# CubeSatPowerSupply.net
KiCad netlist of a schematic drawn in EAGLE
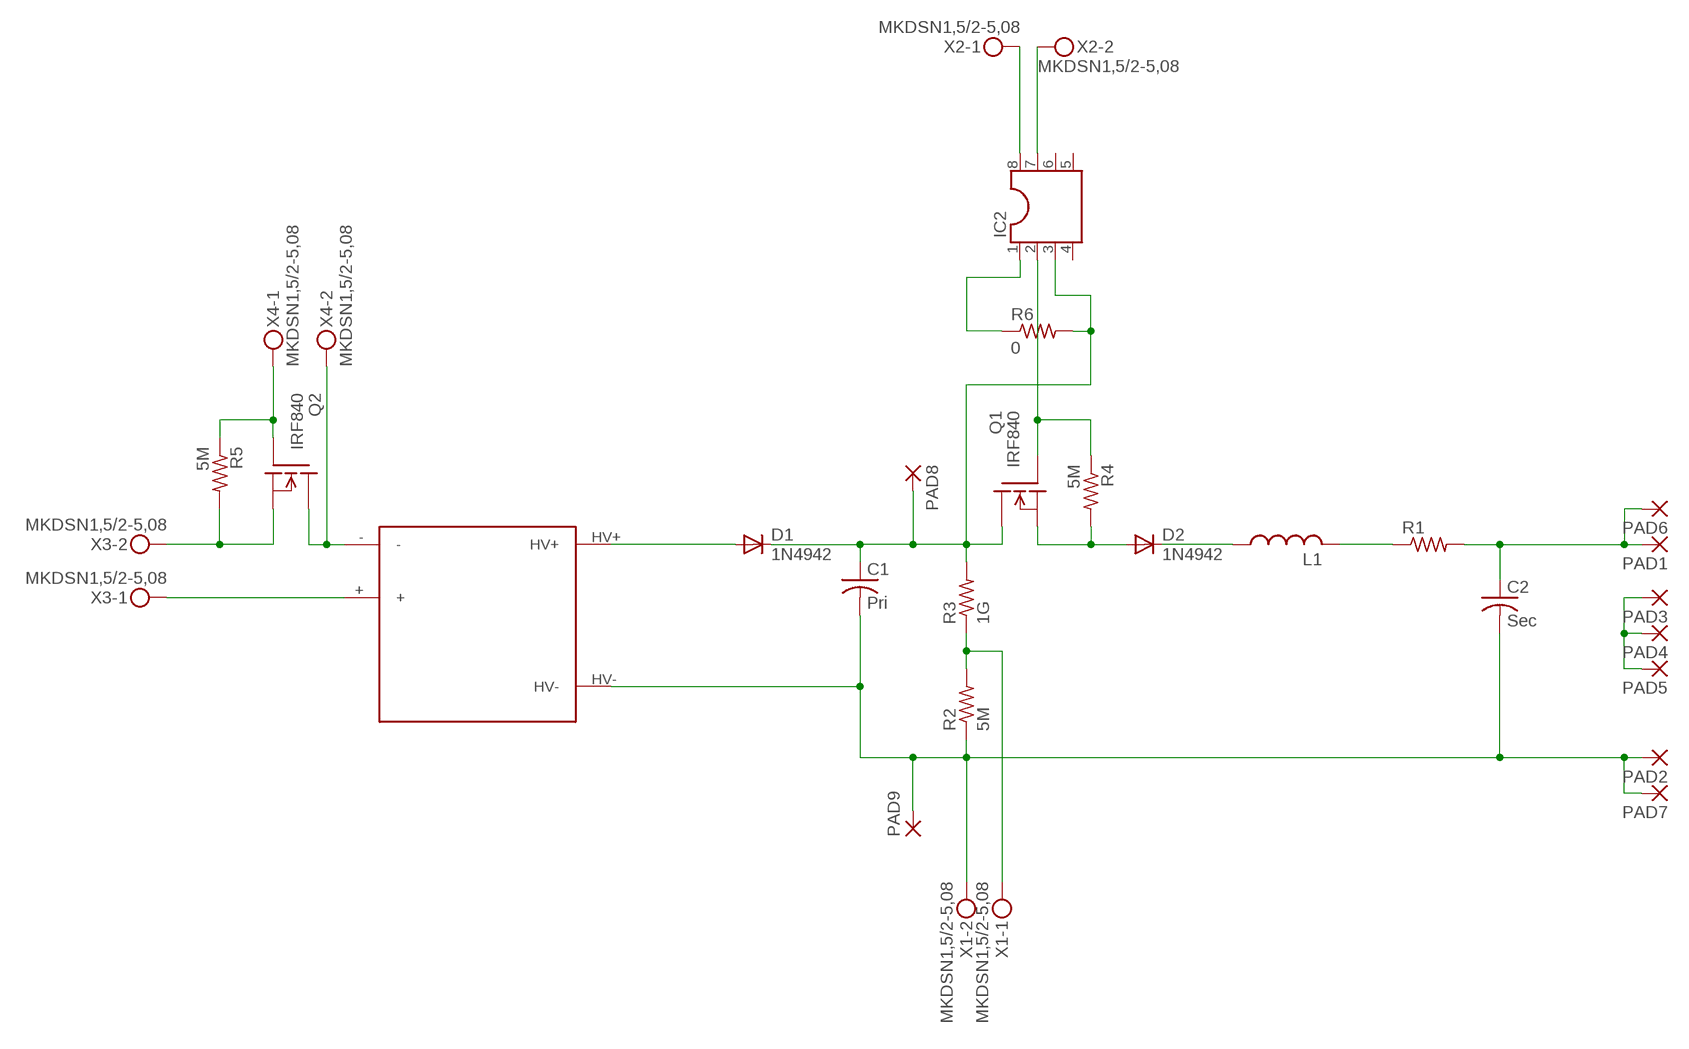
[diagram p0: schematic, sheet 1]

(export (version "E")
  (design (tool "Eeschema 10.0.6"))
  (components
    (comp (ref "C1")
      (value "Pri")
      (footprint "eagle-import:C325-182X374")
      (libsource (lib "eagle-import") (part "C-US325-182X374"))
    )
    (comp (ref "C2")
      (value "Sec")
      (footprint "eagle-import:C325-182X374")
      (libsource (lib "eagle-import") (part "C-US325-182X374"))
    )
    (comp (ref "D1")
      (value "1N4942")
      (footprint "eagle-import:DO41-10")
      (libsource (lib "eagle-import") (part "1N4942"))
    )
    (comp (ref "D2")
      (value "1N4942")
      (footprint "eagle-import:DO41-10")
      (libsource (lib "eagle-import") (part "1N4942"))
    )
    (comp (ref "IC2")
      (value "DIL8")
      (footprint "eagle-import:DIL08")
      (libsource (lib "eagle-import") (part "DIL8"))
    )
    (comp (ref "L1")
      (value "L-US0207/12")
      (footprint "eagle-import:0207_12")
      (libsource (lib "eagle-import") (part "L-US0207/12"))
    )
    (comp (ref "PAD1")
      (value "2,54/1,0")
      (footprint "eagle-import:2,54_1,0")
      (libsource (lib "eagle-import") (part "2,54/1,0"))
    )
    (comp (ref "PAD2")
      (value "2,54/1,0")
      (footprint "eagle-import:2,54_1,0")
      (libsource (lib "eagle-import") (part "2,54/1,0"))
    )
    (comp (ref "PAD3")
      (value "2,54/1,0")
      (footprint "eagle-import:2,54_1,0")
      (libsource (lib "eagle-import") (part "2,54/1,0"))
    )
    (comp (ref "PAD4")
      (value "2,54/1,0")
      (footprint "eagle-import:2,54_1,0")
      (libsource (lib "eagle-import") (part "2,54/1,0"))
    )
    (comp (ref "PAD5")
      (value "2,54/1,0")
      (footprint "eagle-import:2,54_1,0")
      (libsource (lib "eagle-import") (part "2,54/1,0"))
    )
    (comp (ref "PAD6")
      (value "2,54/1,0")
      (footprint "eagle-import:2,54_1,0")
      (libsource (lib "eagle-import") (part "2,54/1,0"))
    )
    (comp (ref "PAD7")
      (value "2,54/1,0")
      (footprint "eagle-import:2,54_1,0")
      (libsource (lib "eagle-import") (part "2,54/1,0"))
    )
    (comp (ref "PAD8")
      (value "2,54/1,0")
      (footprint "eagle-import:2,54_1,0")
      (libsource (lib "eagle-import") (part "2,54/1,0"))
    )
    (comp (ref "PAD9")
      (value "2,54/1,0")
      (footprint "eagle-import:2,54_1,0")
      (libsource (lib "eagle-import") (part "2,54/1,0"))
    )
    (comp (ref "Q1")
      (value "IRF840")
      (footprint "eagle-import:TO220")
      (libsource (lib "eagle-import") (part "IRF840"))
    )
    (comp (ref "Q2")
      (value "IRF840")
      (footprint "eagle-import:TO220")
      (libsource (lib "eagle-import") (part "IRF840"))
    )
    (comp (ref "R1")
      (value "R-US_0309/12")
      (footprint "eagle-import:0309_12")
      (libsource (lib "eagle-import") (part "R-US_0309/12"))
    )
    (comp (ref "R2")
      (value "5M")
      (footprint "eagle-import:0207_10")
      (libsource (lib "eagle-import") (part "R-US_0207/10"))
    )
    (comp (ref "R3")
      (value "1G")
      (footprint "eagle-import:0207_10")
      (libsource (lib "eagle-import") (part "R-US_0207/10"))
    )
    (comp (ref "R4")
      (value "5M")
      (footprint "eagle-import:0207_10")
      (libsource (lib "eagle-import") (part "R-US_0207/10"))
    )
    (comp (ref "R5")
      (value "5M")
      (footprint "eagle-import:0207_10")
      (libsource (lib "eagle-import") (part "R-US_0207/10"))
    )
    (comp (ref "R6")
      (value "0")
      (footprint "eagle-import:0207_10")
      (libsource (lib "eagle-import") (part "R-US_0207/10"))
    )
    (comp (ref "U$1") (value "Q5") (footprint "eagle-import:Q5") (libsource (lib "eagle-import") (part "Q5")))
    (comp (ref "X1")
      (value "MKDSN1,5/2-5,08")
      (footprint "eagle-import:MKDSN1,5_2-5,08")
      (fields (field (name "MPN") "MKDSN 1,5/2-5.08"))
      (libsource (lib "eagle-import") (part "MKDSN1,5/2-5,08"))
    )
    (comp (ref "X2")
      (value "MKDSN1,5/2-5,08")
      (footprint "eagle-import:MKDSN1,5_2-5,08")
      (fields (field (name "MPN") "MKDSN 1,5/2-5.08"))
      (libsource (lib "eagle-import") (part "MKDSN1,5/2-5,08"))
    )
    (comp (ref "X3")
      (value "MKDSN1,5/2-5,08")
      (footprint "eagle-import:MKDSN1,5_2-5,08")
      (fields (field (name "MPN") "MKDSN 1,5/2-5.08"))
      (libsource (lib "eagle-import") (part "MKDSN1,5/2-5,08"))
    )
    (comp (ref "X4")
      (value "MKDSN1,5/2-5,08")
      (footprint "eagle-import:MKDSN1,5_2-5,08")
      (fields (field (name "MPN") "MKDSN 1,5/2-5.08"))
      (libsource (lib "eagle-import") (part "MKDSN1,5/2-5,08"))
    )
  )
  (nets
    (net (code "1") (name "Net-(D1-PadA)") (class "Default")
      (node (ref "D1") (pin "A") (pinfunction "A_A") (pintype "passive"))
      (node (ref "U$1") (pin "HV+") (pinfunction "HV+_HV+") (pintype "bidirectional"))
    )
    (net (code "2") (name "Net-(D2-PadC)") (class "Default")
      (node (ref "D2") (pin "C") (pinfunction "C_C") (pintype "passive"))
      (node (ref "L1") (pin "1") (pinfunction "1_1") (pintype "passive"))
    )
    (net (code "3") (name "Net-(IC2-Pad1)") (class "Default")
      (node (ref "IC2") (pin "1") (pinfunction "1_1") (pintype "passive"))
      (node (ref "R6") (pin "1") (pinfunction "1_1") (pintype "passive"))
    )
    (net (code "4") (name "Net-(L1-Pad2)") (class "Default")
      (node (ref "L1") (pin "2") (pinfunction "2_2") (pintype "passive"))
      (node (ref "R1") (pin "1") (pinfunction "1_1") (pintype "passive"))
    )
    (net (code "5") (name "Net-(PAD1-P)") (class "Default")
      (node (ref "C2") (pin "1") (pinfunction "1_1") (pintype "passive"))
      (node (ref "PAD1") (pin "1") (pinfunction "P_1") (pintype "passive"))
      (node (ref "PAD6") (pin "1") (pinfunction "P_1") (pintype "passive"))
      (node (ref "R1") (pin "2") (pinfunction "2_2") (pintype "passive"))
    )
    (net (code "6") (name "Net-(PAD2-P)") (class "Default")
      (node (ref "C1") (pin "2") (pinfunction "2_2") (pintype "passive"))
      (node (ref "C2") (pin "2") (pinfunction "2_2") (pintype "passive"))
      (node (ref "PAD2") (pin "1") (pinfunction "P_1") (pintype "passive"))
      (node (ref "PAD7") (pin "1") (pinfunction "P_1") (pintype "passive"))
      (node (ref "PAD9") (pin "1") (pinfunction "P_1") (pintype "passive"))
      (node (ref "R2") (pin "1") (pinfunction "1_1") (pintype "passive"))
      (node (ref "U$1") (pin "HV-") (pinfunction "HV-_HV-") (pintype "bidirectional"))
      (node (ref "X1") (pin "2") (pinfunction "KL_2") (pintype "passive"))
    )
    (net (code "7") (name "Net-(PAD3-P)") (class "Default")
      (node (ref "PAD3") (pin "1") (pinfunction "P_1") (pintype "passive"))
      (node (ref "PAD4") (pin "1") (pinfunction "P_1") (pintype "passive"))
      (node (ref "PAD5") (pin "1") (pinfunction "P_1") (pintype "passive"))
    )
    (net (code "8") (name "Net-(PAD8-P)") (class "Default")
      (node (ref "C1") (pin "1") (pinfunction "1_1") (pintype "passive"))
      (node (ref "D1") (pin "C") (pinfunction "C_C") (pintype "passive"))
      (node (ref "IC2") (pin "3") (pinfunction "3_3") (pintype "passive"))
      (node (ref "PAD8") (pin "1") (pinfunction "P_1") (pintype "passive"))
      (node (ref "Q1") (pin "2") (pinfunction "D_2") (pintype "passive"))
      (node (ref "R3") (pin "2") (pinfunction "2_2") (pintype "passive"))
      (node (ref "R6") (pin "2") (pinfunction "2_2") (pintype "passive"))
    )
    (net (code "9") (name "Net-(Q1-G)") (class "Default")
      (node (ref "IC2") (pin "2") (pinfunction "2_2") (pintype "passive"))
      (node (ref "Q1") (pin "1") (pinfunction "G_1") (pintype "passive"))
      (node (ref "R4") (pin "1") (pinfunction "1_1") (pintype "passive"))
    )
    (net (code "10") (name "Net-(Q1-S)") (class "Default")
      (node (ref "D2") (pin "A") (pinfunction "A_A") (pintype "passive"))
      (node (ref "Q1") (pin "3") (pinfunction "S_3") (pintype "passive"))
      (node (ref "R4") (pin "2") (pinfunction "2_2") (pintype "passive"))
    )
    (net (code "11") (name "Net-(Q2-D)") (class "Default")
      (node (ref "Q2") (pin "2") (pinfunction "D_2") (pintype "passive"))
      (node (ref "U$1") (pin "-") (pinfunction "-_-") (pintype "bidirectional"))
      (node (ref "X4") (pin "2") (pinfunction "KL_2") (pintype "passive"))
    )
    (net (code "12") (name "Net-(Q2-G)") (class "Default")
      (node (ref "Q2") (pin "1") (pinfunction "G_1") (pintype "passive"))
      (node (ref "R5") (pin "1") (pinfunction "1_1") (pintype "passive"))
      (node (ref "X4") (pin "1") (pinfunction "KL_1") (pintype "passive"))
    )
    (net (code "13") (name "Net-(Q2-S)") (class "Default")
      (node (ref "Q2") (pin "3") (pinfunction "S_3") (pintype "passive"))
      (node (ref "R5") (pin "2") (pinfunction "2_2") (pintype "passive"))
      (node (ref "X3") (pin "2") (pinfunction "KL_2") (pintype "passive"))
    )
    (net (code "14") (name "Net-(X1A-KL)") (class "Default")
      (node (ref "R2") (pin "2") (pinfunction "2_2") (pintype "passive"))
      (node (ref "R3") (pin "1") (pinfunction "1_1") (pintype "passive"))
      (node (ref "X1") (pin "1") (pinfunction "KL_1") (pintype "passive"))
    )
    (net (code "15") (name "Net-(X2A-KL)") (class "Default")
      (node (ref "IC2") (pin "8") (pinfunction "8_8") (pintype "passive"))
      (node (ref "X2") (pin "1") (pinfunction "KL_1") (pintype "passive"))
    )
    (net (code "16") (name "Net-(X2B-KL)") (class "Default")
      (node (ref "IC2") (pin "7") (pinfunction "7_7") (pintype "passive"))
      (node (ref "X2") (pin "2") (pinfunction "KL_2") (pintype "passive"))
    )
    (net (code "17") (name "Net-(X3A-KL)") (class "Default")
      (node (ref "U$1") (pin "+") (pinfunction "+_+") (pintype "bidirectional"))
      (node (ref "X3") (pin "1") (pinfunction "KL_1") (pintype "passive"))
    )
    (net (code "18") (name "unconnected-(IC2-Pad4)") (class "Default")
      (node (ref "IC2") (pin "4") (pinfunction "4_4") (pintype "passive"))
    )
    (net (code "19") (name "unconnected-(IC2-Pad5)") (class "Default")
      (node (ref "IC2") (pin "5") (pinfunction "5_5") (pintype "passive"))
    )
    (net (code "20") (name "unconnected-(IC2-Pad6)") (class "Default")
      (node (ref "IC2") (pin "6") (pinfunction "6_6") (pintype "passive"))
    )
  )
)
